# ll_start.net
KiCad netlist of a schematic drawn in EAGLE
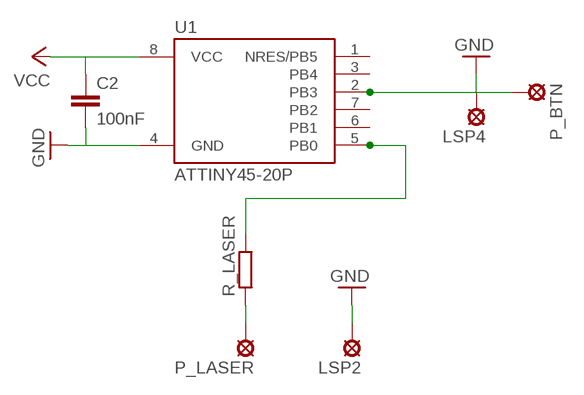
[diagram p0: schematic, sheet 1]

(export (version "E")
  (design (tool "Eeschema 10.0.6"))
  (components
    (comp (ref "C2")
      (value "100nF")
      (footprint "eagle-import:C025-025X050")
      (libsource (lib "eagle-import") (part "C-EU025-025X050"))
    )
    (comp (ref "LSP2")
      (value "LSP10")
      (footprint "eagle-import:LSP10")
      (libsource (lib "eagle-import") (part "LSP10"))
    )
    (comp (ref "LSP4")
      (value "LSP10")
      (footprint "eagle-import:LSP10")
      (libsource (lib "eagle-import") (part "LSP10"))
    )
    (comp (ref "P_BTN")
      (value "LSP10")
      (footprint "eagle-import:LSP10")
      (libsource (lib "eagle-import") (part "LSP10"))
    )
    (comp (ref "P_LASER")
      (value "LSP10")
      (footprint "eagle-import:LSP10")
      (libsource (lib "eagle-import") (part "LSP10"))
    )
    (comp (ref "R_LASER")
      (value "R-EU_0204/7")
      (footprint "eagle-import:0204_7")
      (libsource (lib "eagle-import") (part "R-EU_0204/7"))
    )
    (comp (ref "U1")
      (value "ATTINY45-20P")
      (footprint "eagle-import:PDIP08_300MIL")
      (libsource (lib "eagle-import") (part "ATTINY45P-20"))
    )
  )
  (nets
    (net (code "1") (name "GND") (class "Default")
      (node (ref "C2") (pin "2") (pinfunction "2_2") (pintype "passive"))
      (node (ref "LSP2") (pin "MP") (pinfunction "MP_MP") (pintype "passive"))
      (node (ref "LSP4") (pin "MP") (pinfunction "MP_MP") (pintype "passive"))
      (node (ref "U1") (pin "4") (pinfunction "GND_4") (pintype "power_in"))
    )
    (net (code "2") (name "Net-(P_LASER-PadMP)") (class "Default")
      (node (ref "P_LASER") (pin "MP") (pinfunction "MP_MP") (pintype "passive"))
      (node (ref "R_LASER") (pin "1") (pinfunction "1_1") (pintype "passive"))
    )
    (net (code "3") (name "Net-(U1-PB0)") (class "Default")
      (node (ref "R_LASER") (pin "2") (pinfunction "2_2") (pintype "passive"))
      (node (ref "U1") (pin "5") (pinfunction "PB0_5") (pintype "bidirectional"))
    )
    (net (code "4") (name "Net-(U1-PB3)") (class "Default")
      (node (ref "P_BTN") (pin "MP") (pinfunction "MP_MP") (pintype "passive"))
      (node (ref "U1") (pin "2") (pinfunction "PB3_2") (pintype "bidirectional"))
    )
    (net (code "5") (name "VCC") (class "Default")
      (node (ref "C2") (pin "1") (pinfunction "1_1") (pintype "passive"))
      (node (ref "U1") (pin "8") (pinfunction "VCC_8") (pintype "power_in"))
    )
    (net (code "6") (name "unconnected-(U1-NRES{slash}PB5-Pad1)") (class "Default")
      (node (ref "U1") (pin "1") (pinfunction "NRES/PB5_1") (pintype "bidirectional"))
    )
    (net (code "7") (name "unconnected-(U1-PB1-Pad6)") (class "Default")
      (node (ref "U1") (pin "6") (pinfunction "PB1_6") (pintype "bidirectional"))
    )
    (net (code "8") (name "unconnected-(U1-PB2-Pad7)") (class "Default")
      (node (ref "U1") (pin "7") (pinfunction "PB2_7") (pintype "bidirectional"))
    )
    (net (code "9") (name "unconnected-(U1-PB4-Pad3)") (class "Default")
      (node (ref "U1") (pin "3") (pinfunction "PB4_3") (pintype "bidirectional"))
    )
  )
)
